# TripleWing.net
KiCad netlist of a schematic drawn in EAGLE
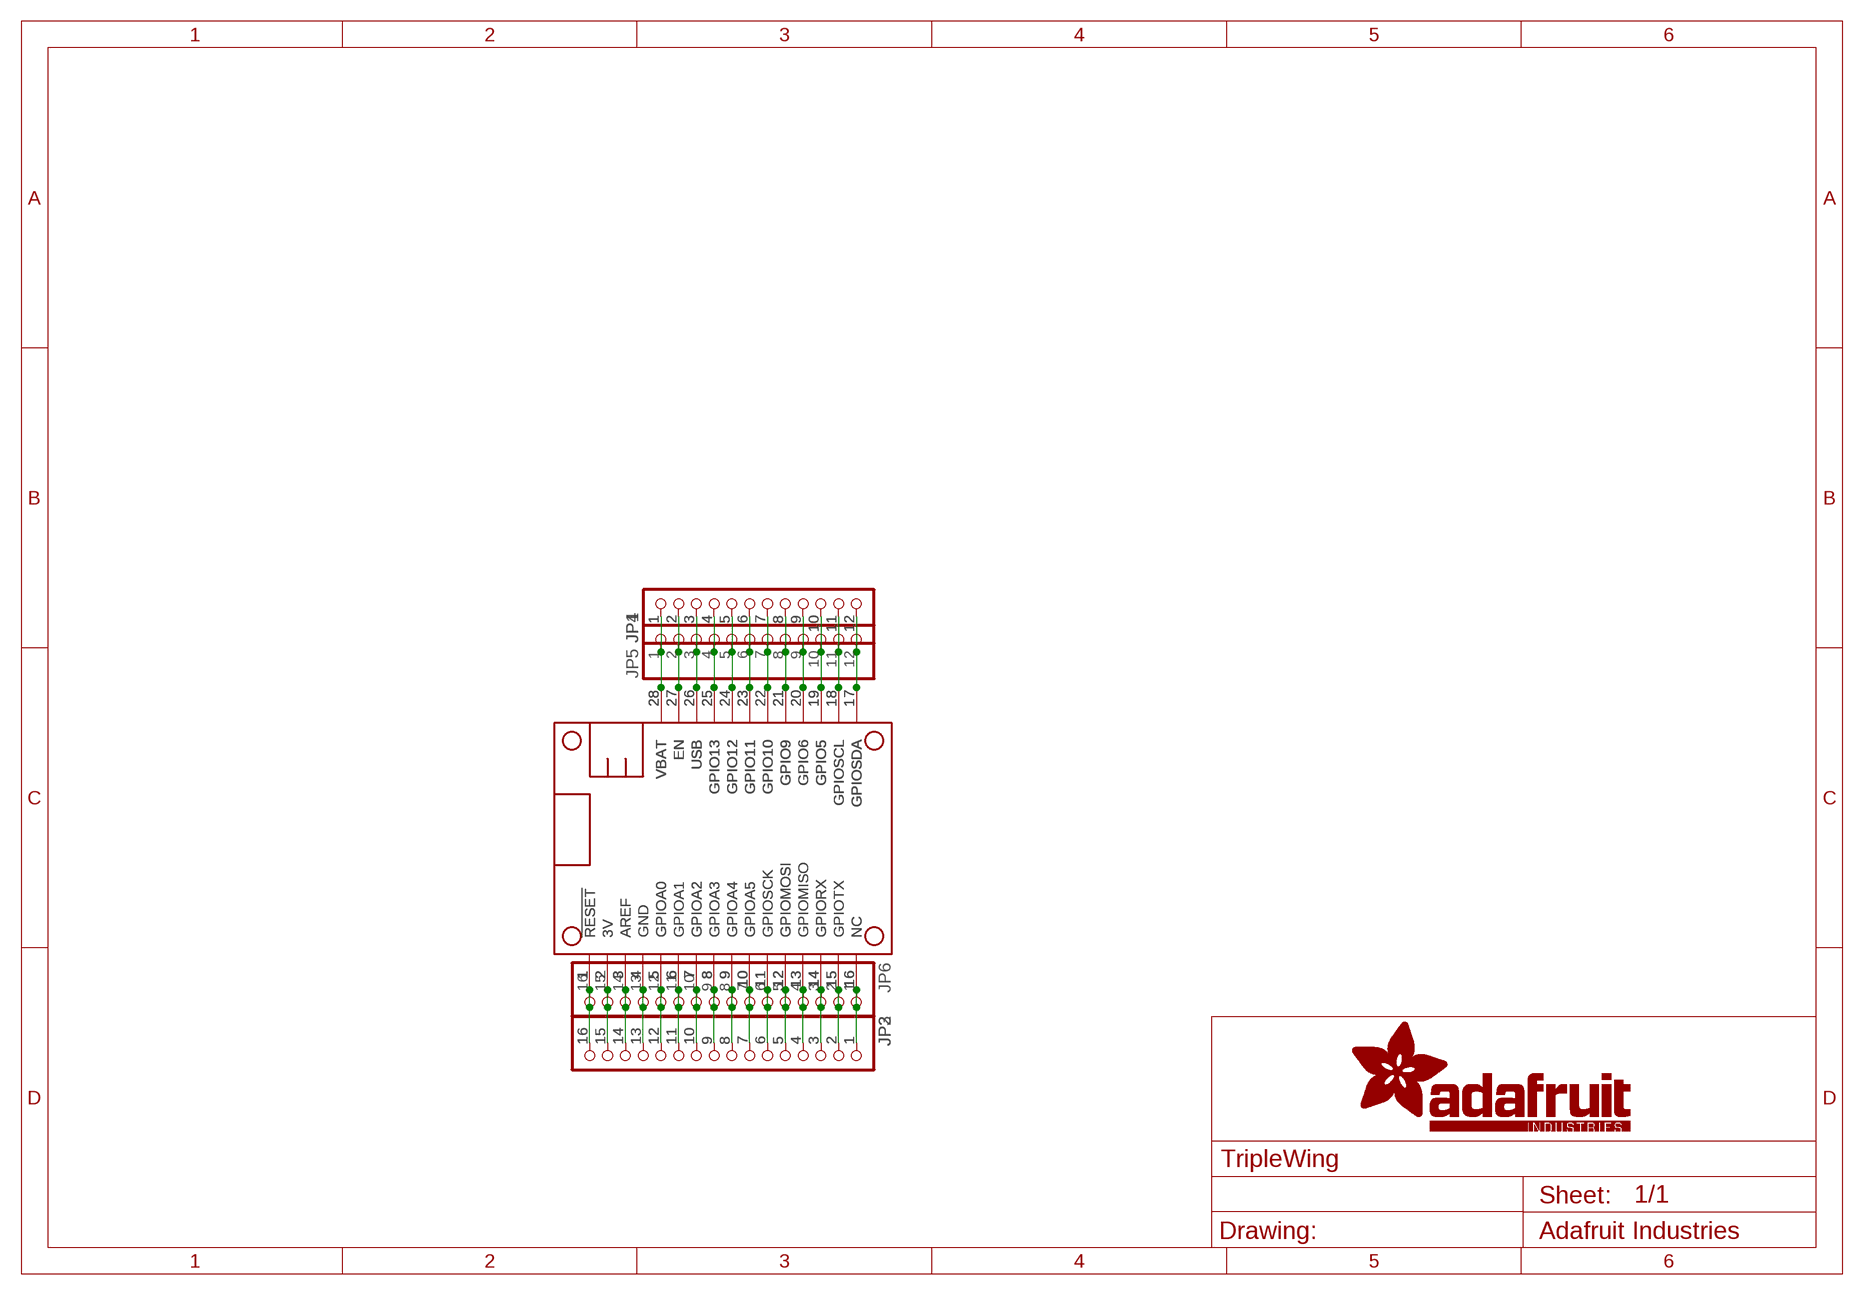
[diagram p0: schematic, sheet 1]

(export (version "E")
  (design (tool "Eeschema 10.0.6"))
  (components
    (comp (ref "JP1")
      (value "HEADER-1X1276MIL")
      (footprint "eagle-import:1X12_ROUND_76MIL")
      (libsource (lib "eagle-import") (part "HEADER-1X1276MIL"))
    )
    (comp (ref "JP2")
      (value "HEADER-1X16_76MIL")
      (footprint "eagle-import:1X16_ROUND_76MIL")
      (libsource (lib "eagle-import") (part "HEADER-1X16_76MIL"))
    )
    (comp (ref "JP3")
      (value "HEADER-1X16_76MIL")
      (footprint "eagle-import:1X16_ROUND_76MIL")
      (libsource (lib "eagle-import") (part "HEADER-1X16_76MIL"))
    )
    (comp (ref "JP4")
      (value "HEADER-1X1276MIL")
      (footprint "eagle-import:1X12_ROUND_76MIL")
      (libsource (lib "eagle-import") (part "HEADER-1X1276MIL"))
    )
    (comp (ref "JP5")
      (value "HEADER-1X1276MIL")
      (footprint "eagle-import:1X12_ROUND_76MIL")
      (libsource (lib "eagle-import") (part "HEADER-1X1276MIL"))
    )
    (comp (ref "JP6")
      (value "HEADER-1X16_76MIL")
      (footprint "eagle-import:1X16_ROUND_76MIL")
      (libsource (lib "eagle-import") (part "HEADER-1X16_76MIL"))
    )
    (comp (ref "MS1")
      (value "FEATHERWING_NODIM")
      (footprint "eagle-import:FEATHERWING_DIM")
      (libsource (lib "eagle-import") (part "FEATHERWING_NODIM"))
    )
    (comp (ref "MS2")
      (value "FEATHERWING_NODIM")
      (footprint "eagle-import:FEATHERWING_DIM")
      (libsource (lib "eagle-import") (part "FEATHERWING_NODIM"))
    )
    (comp (ref "MS3")
      (value "FEATHERWING_NODIM")
      (footprint "eagle-import:FEATHERWING_DIM")
      (libsource (lib "eagle-import") (part "FEATHERWING_NODIM"))
    )
  )
  (nets
    (net (code "1") (name "Net-(MS1-3V)") (class "Default")
      (node (ref "JP2") (pin "15") (pinfunction "15_15") (pintype "passive"))
      (node (ref "JP3") (pin "15") (pinfunction "15_15") (pintype "passive"))
      (node (ref "JP6") (pin "15") (pinfunction "15_15") (pintype "passive"))
      (node (ref "MS1") (pin "2") (pinfunction "3V_2") (pintype "power_in"))
      (node (ref "MS2") (pin "2") (pinfunction "3V_2") (pintype "power_in"))
      (node (ref "MS3") (pin "2") (pinfunction "3V_2") (pintype "power_in"))
    )
    (net (code "2") (name "Net-(MS1-AREF)") (class "Default")
      (node (ref "JP2") (pin "14") (pinfunction "14_14") (pintype "passive"))
      (node (ref "JP3") (pin "14") (pinfunction "14_14") (pintype "passive"))
      (node (ref "JP6") (pin "14") (pinfunction "14_14") (pintype "passive"))
      (node (ref "MS1") (pin "3") (pinfunction "AREF_3") (pintype "passive"))
      (node (ref "MS2") (pin "3") (pinfunction "AREF_3") (pintype "passive"))
      (node (ref "MS3") (pin "3") (pinfunction "AREF_3") (pintype "passive"))
    )
    (net (code "3") (name "Net-(MS1-EN)") (class "Default")
      (node (ref "JP1") (pin "2") (pinfunction "2_2") (pintype "passive"))
      (node (ref "JP4") (pin "2") (pinfunction "2_2") (pintype "passive"))
      (node (ref "JP5") (pin "2") (pinfunction "2_2") (pintype "passive"))
      (node (ref "MS1") (pin "27") (pinfunction "EN_27") (pintype "passive"))
      (node (ref "MS2") (pin "27") (pinfunction "EN_27") (pintype "passive"))
      (node (ref "MS3") (pin "27") (pinfunction "EN_27") (pintype "passive"))
    )
    (net (code "4") (name "Net-(MS1-GND)") (class "Default")
      (node (ref "JP2") (pin "13") (pinfunction "13_13") (pintype "passive"))
      (node (ref "JP3") (pin "13") (pinfunction "13_13") (pintype "passive"))
      (node (ref "JP6") (pin "13") (pinfunction "13_13") (pintype "passive"))
      (node (ref "MS1") (pin "4") (pinfunction "GND_4") (pintype "power_in"))
      (node (ref "MS2") (pin "4") (pinfunction "GND_4") (pintype "power_in"))
      (node (ref "MS3") (pin "4") (pinfunction "GND_4") (pintype "power_in"))
    )
    (net (code "5") (name "Net-(MS1-GPIO5)") (class "Default")
      (node (ref "JP1") (pin "10") (pinfunction "10_10") (pintype "passive"))
      (node (ref "JP4") (pin "10") (pinfunction "10_10") (pintype "passive"))
      (node (ref "JP5") (pin "10") (pinfunction "10_10") (pintype "passive"))
      (node (ref "MS1") (pin "19") (pinfunction "GPIO5_19") (pintype "bidirectional"))
      (node (ref "MS2") (pin "19") (pinfunction "GPIO5_19") (pintype "bidirectional"))
      (node (ref "MS3") (pin "19") (pinfunction "GPIO5_19") (pintype "bidirectional"))
    )
    (net (code "6") (name "Net-(MS1-GPIO6)") (class "Default")
      (node (ref "JP1") (pin "9") (pinfunction "9_9") (pintype "passive"))
      (node (ref "JP4") (pin "9") (pinfunction "9_9") (pintype "passive"))
      (node (ref "JP5") (pin "9") (pinfunction "9_9") (pintype "passive"))
      (node (ref "MS1") (pin "20") (pinfunction "GPIO6_20") (pintype "bidirectional"))
      (node (ref "MS2") (pin "20") (pinfunction "GPIO6_20") (pintype "bidirectional"))
      (node (ref "MS3") (pin "20") (pinfunction "GPIO6_20") (pintype "bidirectional"))
    )
    (net (code "7") (name "Net-(MS1-GPIO9)") (class "Default")
      (node (ref "JP1") (pin "8") (pinfunction "8_8") (pintype "passive"))
      (node (ref "JP4") (pin "8") (pinfunction "8_8") (pintype "passive"))
      (node (ref "JP5") (pin "8") (pinfunction "8_8") (pintype "passive"))
      (node (ref "MS1") (pin "21") (pinfunction "GPIO9_21") (pintype "bidirectional"))
      (node (ref "MS2") (pin "21") (pinfunction "GPIO9_21") (pintype "bidirectional"))
      (node (ref "MS3") (pin "21") (pinfunction "GPIO9_21") (pintype "bidirectional"))
    )
    (net (code "8") (name "Net-(MS1-GPIO10)") (class "Default")
      (node (ref "JP1") (pin "7") (pinfunction "7_7") (pintype "passive"))
      (node (ref "JP4") (pin "7") (pinfunction "7_7") (pintype "passive"))
      (node (ref "JP5") (pin "7") (pinfunction "7_7") (pintype "passive"))
      (node (ref "MS1") (pin "22") (pinfunction "GPIO10_22") (pintype "bidirectional"))
      (node (ref "MS2") (pin "22") (pinfunction "GPIO10_22") (pintype "bidirectional"))
      (node (ref "MS3") (pin "22") (pinfunction "GPIO10_22") (pintype "bidirectional"))
    )
    (net (code "9") (name "Net-(MS1-GPIO11)") (class "Default")
      (node (ref "JP1") (pin "6") (pinfunction "6_6") (pintype "passive"))
      (node (ref "JP4") (pin "6") (pinfunction "6_6") (pintype "passive"))
      (node (ref "JP5") (pin "6") (pinfunction "6_6") (pintype "passive"))
      (node (ref "MS1") (pin "23") (pinfunction "GPIO11_23") (pintype "bidirectional"))
      (node (ref "MS2") (pin "23") (pinfunction "GPIO11_23") (pintype "bidirectional"))
      (node (ref "MS3") (pin "23") (pinfunction "GPIO11_23") (pintype "bidirectional"))
    )
    (net (code "10") (name "Net-(MS1-GPIO12)") (class "Default")
      (node (ref "JP1") (pin "5") (pinfunction "5_5") (pintype "passive"))
      (node (ref "JP4") (pin "5") (pinfunction "5_5") (pintype "passive"))
      (node (ref "JP5") (pin "5") (pinfunction "5_5") (pintype "passive"))
      (node (ref "MS1") (pin "24") (pinfunction "GPIO12_24") (pintype "bidirectional"))
      (node (ref "MS2") (pin "24") (pinfunction "GPIO12_24") (pintype "bidirectional"))
      (node (ref "MS3") (pin "24") (pinfunction "GPIO12_24") (pintype "bidirectional"))
    )
    (net (code "11") (name "Net-(MS1-GPIO13)") (class "Default")
      (node (ref "JP1") (pin "4") (pinfunction "4_4") (pintype "passive"))
      (node (ref "JP4") (pin "4") (pinfunction "4_4") (pintype "passive"))
      (node (ref "JP5") (pin "4") (pinfunction "4_4") (pintype "passive"))
      (node (ref "MS1") (pin "25") (pinfunction "GPIO13_25") (pintype "bidirectional"))
      (node (ref "MS2") (pin "25") (pinfunction "GPIO13_25") (pintype "bidirectional"))
      (node (ref "MS3") (pin "25") (pinfunction "GPIO13_25") (pintype "bidirectional"))
    )
    (net (code "12") (name "Net-(MS1-GPIOA0)") (class "Default")
      (node (ref "JP2") (pin "12") (pinfunction "12_12") (pintype "passive"))
      (node (ref "JP3") (pin "12") (pinfunction "12_12") (pintype "passive"))
      (node (ref "JP6") (pin "12") (pinfunction "12_12") (pintype "passive"))
      (node (ref "MS1") (pin "5") (pinfunction "GPIOA0_5") (pintype "bidirectional"))
      (node (ref "MS2") (pin "5") (pinfunction "GPIOA0_5") (pintype "bidirectional"))
      (node (ref "MS3") (pin "5") (pinfunction "GPIOA0_5") (pintype "bidirectional"))
    )
    (net (code "13") (name "Net-(MS1-GPIOA1)") (class "Default")
      (node (ref "JP2") (pin "11") (pinfunction "11_11") (pintype "passive"))
      (node (ref "JP3") (pin "11") (pinfunction "11_11") (pintype "passive"))
      (node (ref "JP6") (pin "11") (pinfunction "11_11") (pintype "passive"))
      (node (ref "MS1") (pin "6") (pinfunction "GPIOA1_6") (pintype "bidirectional"))
      (node (ref "MS2") (pin "6") (pinfunction "GPIOA1_6") (pintype "bidirectional"))
      (node (ref "MS3") (pin "6") (pinfunction "GPIOA1_6") (pintype "bidirectional"))
    )
    (net (code "14") (name "Net-(MS1-GPIOA2)") (class "Default")
      (node (ref "JP2") (pin "10") (pinfunction "10_10") (pintype "passive"))
      (node (ref "JP3") (pin "10") (pinfunction "10_10") (pintype "passive"))
      (node (ref "JP6") (pin "10") (pinfunction "10_10") (pintype "passive"))
      (node (ref "MS1") (pin "7") (pinfunction "GPIOA2_7") (pintype "bidirectional"))
      (node (ref "MS2") (pin "7") (pinfunction "GPIOA2_7") (pintype "bidirectional"))
      (node (ref "MS3") (pin "7") (pinfunction "GPIOA2_7") (pintype "bidirectional"))
    )
    (net (code "15") (name "Net-(MS1-GPIOA3)") (class "Default")
      (node (ref "JP2") (pin "9") (pinfunction "9_9") (pintype "passive"))
      (node (ref "JP3") (pin "9") (pinfunction "9_9") (pintype "passive"))
      (node (ref "JP6") (pin "9") (pinfunction "9_9") (pintype "passive"))
      (node (ref "MS1") (pin "8") (pinfunction "GPIOA3_8") (pintype "bidirectional"))
      (node (ref "MS2") (pin "8") (pinfunction "GPIOA3_8") (pintype "bidirectional"))
      (node (ref "MS3") (pin "8") (pinfunction "GPIOA3_8") (pintype "bidirectional"))
    )
    (net (code "16") (name "Net-(MS1-GPIOA4)") (class "Default")
      (node (ref "JP2") (pin "8") (pinfunction "8_8") (pintype "passive"))
      (node (ref "JP3") (pin "8") (pinfunction "8_8") (pintype "passive"))
      (node (ref "JP6") (pin "8") (pinfunction "8_8") (pintype "passive"))
      (node (ref "MS1") (pin "9") (pinfunction "GPIOA4_9") (pintype "bidirectional"))
      (node (ref "MS2") (pin "9") (pinfunction "GPIOA4_9") (pintype "bidirectional"))
      (node (ref "MS3") (pin "9") (pinfunction "GPIOA4_9") (pintype "bidirectional"))
    )
    (net (code "17") (name "Net-(MS1-GPIOA5)") (class "Default")
      (node (ref "JP2") (pin "7") (pinfunction "7_7") (pintype "passive"))
      (node (ref "JP3") (pin "7") (pinfunction "7_7") (pintype "passive"))
      (node (ref "JP6") (pin "7") (pinfunction "7_7") (pintype "passive"))
      (node (ref "MS1") (pin "10") (pinfunction "GPIOA5_10") (pintype "bidirectional"))
      (node (ref "MS2") (pin "10") (pinfunction "GPIOA5_10") (pintype "bidirectional"))
      (node (ref "MS3") (pin "10") (pinfunction "GPIOA5_10") (pintype "bidirectional"))
    )
    (net (code "18") (name "Net-(MS1-GPIOMISO)") (class "Default")
      (node (ref "JP2") (pin "4") (pinfunction "4_4") (pintype "passive"))
      (node (ref "JP3") (pin "4") (pinfunction "4_4") (pintype "passive"))
      (node (ref "JP6") (pin "4") (pinfunction "4_4") (pintype "passive"))
      (node (ref "MS1") (pin "13") (pinfunction "GPIOMISO_13") (pintype "bidirectional"))
      (node (ref "MS2") (pin "13") (pinfunction "GPIOMISO_13") (pintype "bidirectional"))
      (node (ref "MS3") (pin "13") (pinfunction "GPIOMISO_13") (pintype "bidirectional"))
    )
    (net (code "19") (name "Net-(MS1-GPIOMOSI)") (class "Default")
      (node (ref "JP2") (pin "5") (pinfunction "5_5") (pintype "passive"))
      (node (ref "JP3") (pin "5") (pinfunction "5_5") (pintype "passive"))
      (node (ref "JP6") (pin "5") (pinfunction "5_5") (pintype "passive"))
      (node (ref "MS1") (pin "12") (pinfunction "GPIOMOSI_12") (pintype "bidirectional"))
      (node (ref "MS2") (pin "12") (pinfunction "GPIOMOSI_12") (pintype "bidirectional"))
      (node (ref "MS3") (pin "12") (pinfunction "GPIOMOSI_12") (pintype "bidirectional"))
    )
    (net (code "20") (name "Net-(MS1-GPIORX)") (class "Default")
      (node (ref "JP2") (pin "3") (pinfunction "3_3") (pintype "passive"))
      (node (ref "JP3") (pin "3") (pinfunction "3_3") (pintype "passive"))
      (node (ref "JP6") (pin "3") (pinfunction "3_3") (pintype "passive"))
      (node (ref "MS1") (pin "14") (pinfunction "GPIORX_14") (pintype "bidirectional"))
      (node (ref "MS2") (pin "14") (pinfunction "GPIORX_14") (pintype "bidirectional"))
      (node (ref "MS3") (pin "14") (pinfunction "GPIORX_14") (pintype "bidirectional"))
    )
    (net (code "21") (name "Net-(MS1-GPIOSCK)") (class "Default")
      (node (ref "JP2") (pin "6") (pinfunction "6_6") (pintype "passive"))
      (node (ref "JP3") (pin "6") (pinfunction "6_6") (pintype "passive"))
      (node (ref "JP6") (pin "6") (pinfunction "6_6") (pintype "passive"))
      (node (ref "MS1") (pin "11") (pinfunction "GPIOSCK_11") (pintype "bidirectional"))
      (node (ref "MS2") (pin "11") (pinfunction "GPIOSCK_11") (pintype "bidirectional"))
      (node (ref "MS3") (pin "11") (pinfunction "GPIOSCK_11") (pintype "bidirectional"))
    )
    (net (code "22") (name "Net-(MS1-GPIOSCL)") (class "Default")
      (node (ref "JP1") (pin "11") (pinfunction "11_11") (pintype "passive"))
      (node (ref "JP4") (pin "11") (pinfunction "11_11") (pintype "passive"))
      (node (ref "JP5") (pin "11") (pinfunction "11_11") (pintype "passive"))
      (node (ref "MS1") (pin "18") (pinfunction "GPIOSCL_18") (pintype "bidirectional"))
      (node (ref "MS2") (pin "18") (pinfunction "GPIOSCL_18") (pintype "bidirectional"))
      (node (ref "MS3") (pin "18") (pinfunction "GPIOSCL_18") (pintype "bidirectional"))
    )
    (net (code "23") (name "Net-(MS1-GPIOSDA)") (class "Default")
      (node (ref "JP1") (pin "12") (pinfunction "12_12") (pintype "passive"))
      (node (ref "JP4") (pin "12") (pinfunction "12_12") (pintype "passive"))
      (node (ref "JP5") (pin "12") (pinfunction "12_12") (pintype "passive"))
      (node (ref "MS1") (pin "17") (pinfunction "GPIOSDA_17") (pintype "bidirectional"))
      (node (ref "MS2") (pin "17") (pinfunction "GPIOSDA_17") (pintype "bidirectional"))
      (node (ref "MS3") (pin "17") (pinfunction "GPIOSDA_17") (pintype "bidirectional"))
    )
    (net (code "24") (name "Net-(MS1-GPIOTX)") (class "Default")
      (node (ref "JP2") (pin "2") (pinfunction "2_2") (pintype "passive"))
      (node (ref "JP3") (pin "2") (pinfunction "2_2") (pintype "passive"))
      (node (ref "JP6") (pin "2") (pinfunction "2_2") (pintype "passive"))
      (node (ref "MS1") (pin "15") (pinfunction "GPIOTX_15") (pintype "bidirectional"))
      (node (ref "MS2") (pin "15") (pinfunction "GPIOTX_15") (pintype "bidirectional"))
      (node (ref "MS3") (pin "15") (pinfunction "GPIOTX_15") (pintype "bidirectional"))
    )
    (net (code "25") (name "Net-(MS1-NC)") (class "Default")
      (node (ref "JP2") (pin "1") (pinfunction "1_1") (pintype "passive"))
      (node (ref "JP3") (pin "1") (pinfunction "1_1") (pintype "passive"))
      (node (ref "JP6") (pin "1") (pinfunction "1_1") (pintype "passive"))
      (node (ref "MS1") (pin "16") (pinfunction "NC_16") (pintype "passive"))
      (node (ref "MS2") (pin "16") (pinfunction "NC_16") (pintype "passive"))
      (node (ref "MS3") (pin "16") (pinfunction "NC_16") (pintype "passive"))
    )
    (net (code "26") (name "Net-(MS1-USB)") (class "Default")
      (node (ref "JP1") (pin "3") (pinfunction "3_3") (pintype "passive"))
      (node (ref "JP4") (pin "3") (pinfunction "3_3") (pintype "passive"))
      (node (ref "JP5") (pin "3") (pinfunction "3_3") (pintype "passive"))
      (node (ref "MS1") (pin "26") (pinfunction "USB_26") (pintype "power_in"))
      (node (ref "MS2") (pin "26") (pinfunction "USB_26") (pintype "power_in"))
      (node (ref "MS3") (pin "26") (pinfunction "USB_26") (pintype "power_in"))
    )
    (net (code "27") (name "Net-(MS1-VBAT)") (class "Default")
      (node (ref "JP1") (pin "1") (pinfunction "1_1") (pintype "passive"))
      (node (ref "JP4") (pin "1") (pinfunction "1_1") (pintype "passive"))
      (node (ref "JP5") (pin "1") (pinfunction "1_1") (pintype "passive"))
      (node (ref "MS1") (pin "28") (pinfunction "VBAT_28") (pintype "power_in"))
      (node (ref "MS2") (pin "28") (pinfunction "VBAT_28") (pintype "power_in"))
      (node (ref "MS3") (pin "28") (pinfunction "VBAT_28") (pintype "power_in"))
    )
    (net (code "28") (name "Net-(MS1-~{RESET})") (class "Default")
      (node (ref "JP2") (pin "16") (pinfunction "16_16") (pintype "passive"))
      (node (ref "JP3") (pin "16") (pinfunction "16_16") (pintype "passive"))
      (node (ref "JP6") (pin "16") (pinfunction "16_16") (pintype "passive"))
      (node (ref "MS1") (pin "1") (pinfunction "~{RESET}_1") (pintype "input"))
      (node (ref "MS2") (pin "1") (pinfunction "~{RESET}_1") (pintype "input"))
      (node (ref "MS3") (pin "1") (pinfunction "~{RESET}_1") (pintype "input"))
    )
  )
)
